# MIKROE262.net
KiCad netlist of a schematic drawn in Altium Designer
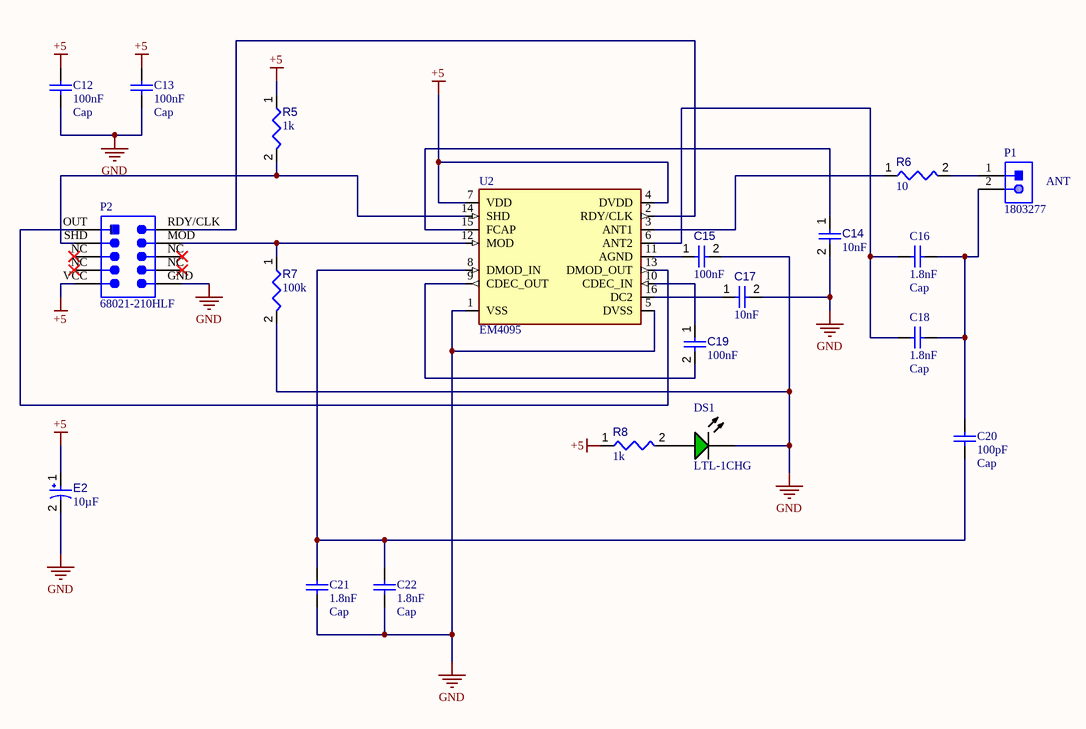
[diagram p0: MIKROE262.SchDoc]

(export (version "E")
  (design (tool "Eeschema 10.0.6"))
  (components
    (comp (ref "C12")
      (value "Cap")
      (footprint "RAD-0.3")
      (description "Capacitor")
      (fields (field (name "ALTIUM_VALUE") "100nF") (field (name "PUBLISHER") "Altium Limited"))
      (libsource (lib "Miscellaneous Devices") (part "Cap"))
    )
    (comp (ref "C13")
      (value "Cap")
      (footprint "RAD-0.3")
      (description "Capacitor")
      (fields (field (name "ALTIUM_VALUE") "100nF") (field (name "PUBLISHER") "Altium Limited"))
      (libsource (lib "Miscellaneous Devices") (part "Cap"))
    )
    (comp (ref "C14")
      (value "10nF")
      (footprint "CAPC0402(1005)60_L")
      (description "Chip Capacitor, 10nF +/-20%, 50V, 0402, Thickness 0.6 mm")
      (fields (field (name "TOLERANCE") "5%") (field (name "Comment") "Capacitor 10nF +/-20% 50V 0402"))
      (libsource (lib "Julian Porro") (part "CAP-NP-2"))
    )
    (comp (ref "C15")
      (value "100nF")
      (footprint "CAPC0402(1005)60_L")
      (description "Chip Capacitor, 100nF +/-20%, 25V, 0402, Thickness 0.6 mm")
      (fields (field (name "TOLERANCE") "10%") (field (name "Comment") "Capacitor 100nF +/-20% 25V 0402"))
      (libsource (lib "Julian Porro") (part "CAP-NP-2"))
    )
    (comp (ref "C16")
      (value "Cap")
      (footprint "RAD-0.3")
      (description "Capacitor")
      (fields (field (name "ALTIUM_VALUE") "1.8nF") (field (name "PUBLISHER") "Altium Limited"))
      (libsource (lib "Miscellaneous Devices") (part "Cap"))
    )
    (comp (ref "C17")
      (value "10nF")
      (footprint "CAPC0402(1005)60_L")
      (description "Chip Capacitor, 10nF +/-20%, 50V, 0402, Thickness 0.6 mm")
      (fields (field (name "TOLERANCE") "5%") (field (name "Comment") "Capacitor 10nF +/-20% 50V 0402"))
      (libsource (lib "Julian Porro") (part "CAP-NP-2"))
    )
    (comp (ref "C18")
      (value "Cap")
      (footprint "RAD-0.3")
      (description "Capacitor")
      (fields (field (name "ALTIUM_VALUE") "1.8nF") (field (name "PUBLISHER") "Altium Limited"))
      (libsource (lib "Miscellaneous Devices") (part "Cap"))
    )
    (comp (ref "C19")
      (value "100nF")
      (footprint "CAPC0402(1005)60_L")
      (description "Chip Capacitor, 100nF +/-20%, 25V, 0402, Thickness 0.6 mm")
      (fields (field (name "TOLERANCE") "10%") (field (name "Comment") "Capacitor 100nF +/-20% 25V 0402"))
      (libsource (lib "Julian Porro") (part "CAP-NP-2"))
    )
    (comp (ref "C20")
      (value "Cap")
      (footprint "RAD-0.3")
      (description "Capacitor")
      (fields (field (name "ALTIUM_VALUE") "100pF") (field (name "PUBLISHER") "Altium Limited"))
      (libsource (lib "Miscellaneous Devices") (part "Cap"))
    )
    (comp (ref "C21")
      (value "Cap")
      (footprint "RAD-0.3")
      (description "Capacitor")
      (fields (field (name "ALTIUM_VALUE") "1.8nF") (field (name "PUBLISHER") "Altium Limited"))
      (libsource (lib "Miscellaneous Devices") (part "Cap"))
    )
    (comp (ref "C22")
      (value "Cap")
      (footprint "RAD-0.3")
      (description "Capacitor")
      (fields (field (name "ALTIUM_VALUE") "1.8nF") (field (name "PUBLISHER") "Altium Limited"))
      (libsource (lib "Miscellaneous Devices") (part "Cap"))
    )
    (comp (ref "DS1")
      (value "LTL-1CHG")
      (footprint "LTST-LTL-1CHG-2")
      (description "LED Uni-Color Green, 100 mW, 30 mA, -55 to 100 degC, 2-Pin THD, RoHS, Bulk")
      (fields (field (name "POWER") "100mW") (field (name "MANUFACTURER") "Lite-On"))
      (libsource (lib "Julian Porro") (part "LED-GREEN-AK-2"))
    )
    (comp (ref "E2")
      (value "10µF")
      (footprint "CAPMP3217X18-T_V")
      (description "Standard Tantalum, 10 uF, +/- 10%, 16 V, -55 to 125 degC, 1206 (3216 Metric), RoHS, Tape and Reel")
      (fields (field (name "TOLERANCE") "10%") (field (name "MANUFACTURER") "AVX"))
      (libsource (lib "Julian Porro") (part "CAP-P-2"))
    )
    (comp (ref "P1")
      (value "1803277")
      (footprint "PHOE-1803277_V")
      (description "Male Header, Pitch 3.81 mm, 1 x 2 Position, Height 7.25 mm, Tail Length 3.4 mm, RoHS, Bulk")
      (fields (field (name "MANUFACTURER") "Phoenix Contact"))
      (libsource (lib "Julian Porro") (part "CN-1P-M-R2"))
    )
    (comp (ref "P2")
      (value "68021-210HLF")
      (footprint "FCI-68021-210HLF-10_V")
      (description "Male Header, Pitch 2.54 mm, 2 x 5 Position, Height 4.83 mm, Tail Length 3.05 mm, Bulk")
      (fields (field (name "MANUFACTURER") "FCI Electronics"))
      (libsource (lib "Julian Porro") (part "CN-2P-M-R10"))
    )
    (comp (ref "R5")
      (value "1k")
      (footprint "RESC1005X40X25ML10T10")
      (description "Chip Resistor, 1 KOhm, +/- 5%, 0.063 W, -55 to 155 degC, 0402 (1005 Metric)")
      (fields (field (name "TOLERANCE") "5%") (field (name "POWER") "63mW"))
      (libsource (lib "Julian Porro") (part "RES-2"))
    )
    (comp (ref "R6")
      (value "10")
      (footprint "RESC1005X40X25ML10T10")
      (description "Chip Resistor, 10 Ohm, +/- 5%, 0.063 W, -55 to 155 degC, 0402 (1005 Metric)")
      (fields (field (name "POWER") "63mW") (field (name "TOLERANCE") "5%"))
      (libsource (lib "Julian Porro") (part "RES-2"))
    )
    (comp (ref "R7")
      (value "100k")
      (footprint "RESC0402(1005)_L")
      (description "Chip Resistor, 100 kOhms, +/-1 %, 63 mW, -55 to 155 degC, 0402")
      (fields (field (name "TOLERANCE") "1%") (field (name "POWER") "63mW"))
      (libsource (lib "Julian Porro") (part "RES-2"))
    )
    (comp (ref "R8")
      (value "1k")
      (footprint "RESC1005X40X25ML10T10")
      (description "Chip Resistor, 1 KOhm, +/- 5%, 0.063 W, -55 to 155 degC, 0402 (1005 Metric)")
      (fields (field (name "TOLERANCE") "5%") (field (name "POWER") "63mW"))
      (libsource (lib "Julian Porro") (part "RES-2"))
    )
    (comp (ref "U2")
      (value "EM4095")
      (footprint "SO16")
      (fields (field (name "MF") "Others"))
      (libsource (lib "EM4095") (part "EM4095"))
    )
  )
  (nets
    (net (code "1") (name "+5") (class "Default")
      (node (ref "C12") (pin "2") (pinfunction "2_2") (pintype "passive"))
      (node (ref "C13") (pin "2") (pinfunction "2_2") (pintype "passive"))
      (node (ref "E2") (pin "1") (pinfunction "1_1") (pintype "passive"))
      (node (ref "P2") (pin "VCC") (pinfunction "9_VCC") (pintype "passive"))
      (node (ref "R5") (pin "1") (pinfunction "1_1") (pintype "passive"))
      (node (ref "R8") (pin "1") (pinfunction "1_1") (pintype "passive"))
      (node (ref "U2") (pin "4") (pinfunction "DVDD_4") (pintype "power_in"))
      (node (ref "U2") (pin "7") (pinfunction "VDD_7") (pintype "power_in"))
    )
    (net (code "2") (name "GND") (class "Default")
      (node (ref "C12") (pin "1") (pinfunction "1_1") (pintype "passive"))
      (node (ref "C13") (pin "1") (pinfunction "1_1") (pintype "passive"))
      (node (ref "C14") (pin "2") (pinfunction "2_2") (pintype "passive"))
      (node (ref "C15") (pin "2") (pinfunction "2_2") (pintype "passive"))
      (node (ref "C17") (pin "2") (pinfunction "2_2") (pintype "passive"))
      (node (ref "C21") (pin "1") (pinfunction "1_1") (pintype "passive"))
      (node (ref "C22") (pin "1") (pinfunction "1_1") (pintype "passive"))
      (node (ref "DS1") (pin "2") (pinfunction "K_2") (pintype "passive"))
      (node (ref "E2") (pin "2") (pinfunction "2_2") (pintype "passive"))
      (node (ref "P2") (pin "GND") (pinfunction "10_GND") (pintype "passive"))
      (node (ref "R7") (pin "2") (pinfunction "2_2") (pintype "passive"))
      (node (ref "U2") (pin "1") (pinfunction "VSS_1") (pintype "power_in"))
      (node (ref "U2") (pin "5") (pinfunction "DVSS_5") (pintype "power_in"))
    )
    (net (code "3") (name "Net-(C16-Pad2)") (class "Default")
      (node (ref "C16") (pin "2") (pinfunction "2_2") (pintype "passive"))
      (node (ref "C18") (pin "2") (pinfunction "2_2") (pintype "passive"))
      (node (ref "C20") (pin "2") (pinfunction "2_2") (pintype "passive"))
      (node (ref "P1") (pin "2") (pinfunction "2_2") (pintype "passive"))
    )
    (net (code "4") (name "Net-(DS1-A)") (class "Default")
      (node (ref "DS1") (pin "1") (pinfunction "A_1") (pintype "passive"))
      (node (ref "R8") (pin "2") (pinfunction "2_2") (pintype "passive"))
    )
    (net (code "5") (name "Net-(P1-Pad1)") (class "Default")
      (node (ref "P1") (pin "1") (pinfunction "1_1") (pintype "passive"))
      (node (ref "R6") (pin "2") (pinfunction "2_2") (pintype "passive"))
    )
    (net (code "6") (name "Net-(P2-1)") (class "Default")
      (node (ref "P2") (pin "OUT") (pinfunction "1_OUT") (pintype "passive"))
      (node (ref "U2") (pin "13") (pinfunction "DMOD_OUT_13") (pintype "output"))
    )
    (net (code "7") (name "Net-(P2-2)") (class "Default")
      (node (ref "P2") (pin "RDY/CLK") (pinfunction "2_RDY/CLK") (pintype "passive"))
      (node (ref "U2") (pin "2") (pinfunction "RDY/CLK_2") (pintype "output"))
    )
    (net (code "8") (name "Net-(P2-3)") (class "Default")
      (node (ref "P2") (pin "SHD") (pinfunction "3_SHD") (pintype "passive"))
      (node (ref "R5") (pin "2") (pinfunction "2_2") (pintype "passive"))
      (node (ref "U2") (pin "14") (pinfunction "SHD_14") (pintype "input"))
    )
    (net (code "9") (name "Net-(P2-4)") (class "Default")
      (node (ref "P2") (pin "MOD") (pinfunction "4_MOD") (pintype "passive"))
      (node (ref "R7") (pin "1") (pinfunction "1_1") (pintype "passive"))
      (node (ref "U2") (pin "12") (pinfunction "MOD_12") (pintype "input"))
    )
    (net (code "10") (name "Net-(U2-AGND)") (class "Default")
      (node (ref "C15") (pin "1") (pinfunction "1_1") (pintype "passive"))
      (node (ref "U2") (pin "11") (pinfunction "AGND_11") (pintype "power_in"))
    )
    (net (code "11") (name "Net-(U2-ANT1)") (class "Default")
      (node (ref "R6") (pin "1") (pinfunction "1_1") (pintype "passive"))
      (node (ref "U2") (pin "3") (pinfunction "ANT1_3") (pintype "passive"))
    )
    (net (code "12") (name "Net-(U2-ANT2)") (class "Default")
      (node (ref "C16") (pin "1") (pinfunction "1_1") (pintype "passive"))
      (node (ref "C18") (pin "1") (pinfunction "1_1") (pintype "passive"))
      (node (ref "U2") (pin "6") (pinfunction "ANT2_6") (pintype "passive"))
    )
    (net (code "13") (name "Net-(U2-CDEC_IN)") (class "Default")
      (node (ref "C19") (pin "1") (pinfunction "1_1") (pintype "passive"))
      (node (ref "U2") (pin "10") (pinfunction "CDEC_IN_10") (pintype "input"))
    )
    (net (code "14") (name "Net-(U2-CDEC_OUT)") (class "Default")
      (node (ref "C19") (pin "2") (pinfunction "2_2") (pintype "passive"))
      (node (ref "U2") (pin "9") (pinfunction "CDEC_OUT_9") (pintype "output"))
    )
    (net (code "15") (name "Net-(U2-DC2)") (class "Default")
      (node (ref "C17") (pin "1") (pinfunction "1_1") (pintype "passive"))
      (node (ref "U2") (pin "16") (pinfunction "DC2_16") (pintype "passive"))
    )
    (net (code "16") (name "Net-(U2-DMOD_IN)") (class "Default")
      (node (ref "C20") (pin "1") (pinfunction "1_1") (pintype "passive"))
      (node (ref "C21") (pin "2") (pinfunction "2_2") (pintype "passive"))
      (node (ref "C22") (pin "2") (pinfunction "2_2") (pintype "passive"))
      (node (ref "U2") (pin "8") (pinfunction "DMOD_IN_8") (pintype "input"))
    )
    (net (code "17") (name "Net-(U2-FCAP)") (class "Default")
      (node (ref "C14") (pin "1") (pinfunction "1_1") (pintype "passive"))
      (node (ref "U2") (pin "15") (pinfunction "FCAP_15") (pintype "passive"))
    )
    (net (code "18") (name "unconnected-(P2-5-PadNC)") (class "Default")
      (node (ref "P2") (pin "NC") (pinfunction "5_NC") (pintype "passive+no_connect"))
    )
    (net (code "19") (name "unconnected-(P2-6-PadNC)") (class "Default")
      (node (ref "P2") (pin "NC") (pinfunction "6_NC") (pintype "passive+no_connect"))
    )
    (net (code "20") (name "unconnected-(P2-7-PadNC)") (class "Default")
      (node (ref "P2") (pin "NC") (pinfunction "7_NC") (pintype "passive+no_connect"))
    )
    (net (code "21") (name "unconnected-(P2-8-PadNC)") (class "Default")
      (node (ref "P2") (pin "NC") (pinfunction "8_NC") (pintype "passive+no_connect"))
    )
  )
)
